# ltk-hall_main_igen.net
KiCad netlist of a schematic drawn in Altium Designer
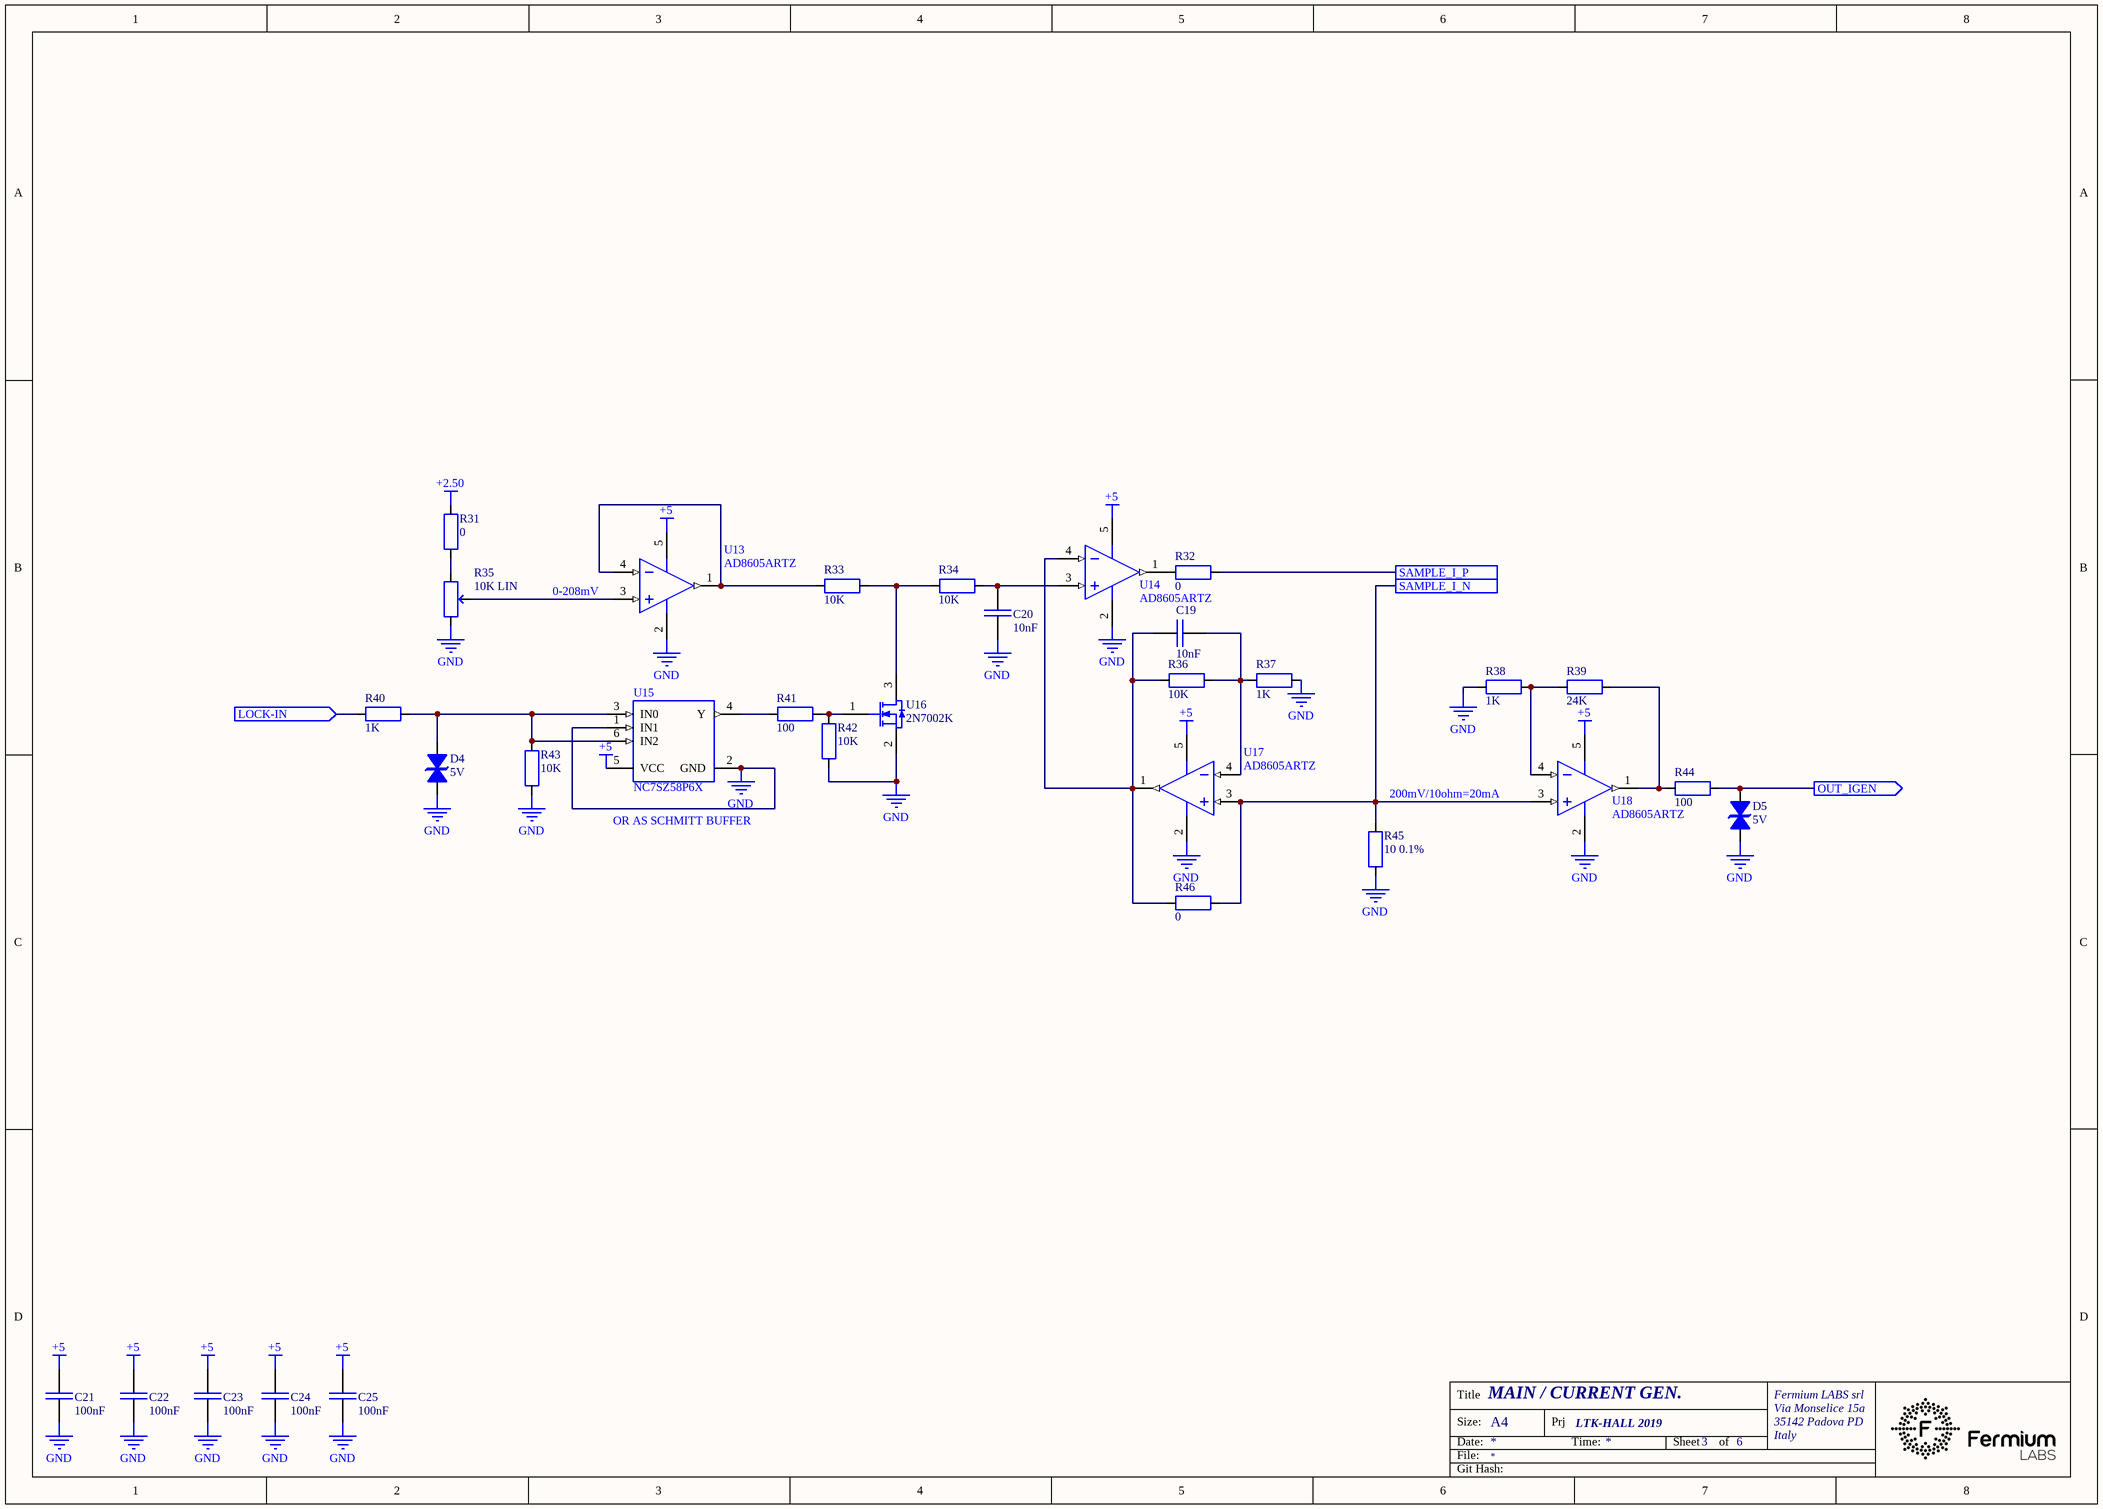
[diagram p0: ltk-hall_main_igen.SchDoc]

(export (version "E")
  (design (tool "Eeschema 10.0.6"))
  (components
    (comp (ref "C19")
      (value "10nF")
      (footprint "CAP 0603_1608")
      (description "CAP SMD MLCC 10nF 50V 0603 X7R")
      (fields (field (name "PART NUMBER") "84e1ebe1-2230-4987-8231-c47d83fa5f7f"))
      (libsource (lib "frmdblib") (part "GENERIC_C"))
    )
    (comp (ref "C20")
      (value "10nF")
      (footprint "CAP 0603_1608")
      (description "CAP SMD MLCC 10nF 50V 0603 X7R")
      (fields (field (name "PART NUMBER") "84e1ebe1-2230-4987-8231-c47d83fa5f7f"))
      (libsource (lib "frmdblib") (part "GENERIC_C"))
    )
    (comp (ref "C21")
      (value "100nF")
      (footprint "CAP 0603_1608")
      (description "CAP SMD MLCC 100nF 25V 0603 X7R")
      (fields (field (name "PART NUMBER") "02841f84-ac15-41b5-9e17-915f8f067828"))
      (libsource (lib "frmdblib") (part "GENERIC_C"))
    )
    (comp (ref "C22")
      (value "100nF")
      (footprint "CAP 0603_1608")
      (description "CAP SMD MLCC 100nF 25V 0603 X7R")
      (fields (field (name "PART NUMBER") "02841f84-ac15-41b5-9e17-915f8f067828"))
      (libsource (lib "frmdblib") (part "GENERIC_C"))
    )
    (comp (ref "C23")
      (value "100nF")
      (footprint "CAP 0603_1608")
      (description "CAP SMD MLCC 100nF 25V 0603 X7R")
      (fields (field (name "PART NUMBER") "02841f84-ac15-41b5-9e17-915f8f067828"))
      (libsource (lib "frmdblib") (part "GENERIC_C"))
    )
    (comp (ref "C24")
      (value "100nF")
      (footprint "CAP 0603_1608")
      (description "CAP SMD MLCC 100nF 25V 0603 X7R")
      (fields (field (name "PART NUMBER") "02841f84-ac15-41b5-9e17-915f8f067828"))
      (libsource (lib "frmdblib") (part "GENERIC_C"))
    )
    (comp (ref "C25")
      (value "100nF")
      (footprint "CAP 0603_1608")
      (description "CAP SMD MLCC 100nF 25V 0603 X7R")
      (fields (field (name "PART NUMBER") "02841f84-ac15-41b5-9e17-915f8f067828"))
      (libsource (lib "frmdblib") (part "GENERIC_C"))
    )
    (comp (ref "D4")
      (value "5V")
      (footprint "SOD523F")
      (description "DIODE SMD TVS 5V BIDIRECTIONAL SOD-523")
      (fields (field (name "PART NUMBER") "daa58212-38e2-4326-a156-8e48058c46f1"))
      (libsource (lib "frmdblib") (part "GENERIC_D_TVS_BI"))
    )
    (comp (ref "D5")
      (value "5V")
      (footprint "SOD523F")
      (description "DIODE SMD TVS 5V BIDIRECTIONAL SOD-523")
      (fields (field (name "PART NUMBER") "daa58212-38e2-4326-a156-8e48058c46f1"))
      (libsource (lib "frmdblib") (part "GENERIC_D_TVS_BI"))
    )
    (comp (ref "R31")
      (value "0")
      (footprint "RES 0603_1608")
      (description "RES SMD 0 OHM 5% 1/10W 0603")
      (fields (field (name "PART NUMBER") "6ae227f9-847f-4766-8522-e11a83531204"))
      (libsource (lib "frmdblib") (part "GENERIC_R"))
    )
    (comp (ref "R32")
      (value "0")
      (footprint "RES 0603_1608")
      (description "RES SMD 0 OHM 5% 1/10W 0603")
      (fields (field (name "PART NUMBER") "6ae227f9-847f-4766-8522-e11a83531204"))
      (libsource (lib "frmdblib") (part "GENERIC_R"))
    )
    (comp (ref "R33")
      (value "10K")
      (footprint "RES 0603_1608")
      (description "RES SMD 10K OHM 1% 1/10W 0603")
      (fields (field (name "PART NUMBER") "93242766-ba1d-462d-b58f-ce1dfc4129c8"))
      (libsource (lib "frmdblib") (part "GENERIC_R"))
    )
    (comp (ref "R34")
      (value "10K")
      (footprint "RES 0603_1608")
      (description "RES SMD 10K OHM 1% 1/10W 0603")
      (fields (field (name "PART NUMBER") "93242766-ba1d-462d-b58f-ce1dfc4129c8"))
      (libsource (lib "frmdblib") (part "GENERIC_R"))
    )
    (comp (ref "R35")
      (value "10K LIN")
      (footprint "2EF88547-EDEF-4A49-A522-C215618D4BC7")
      (description "POT 10K 20% SHAFT 6mmx7.4mm LIN")
      (fields (field (name "PART NUMBER") "3df905ea-1e80-4add-859d-a36edd7f106c"))
      (libsource (lib "frmdblib") (part "GENERIC_R_VAR"))
    )
    (comp (ref "R36")
      (value "10K")
      (footprint "RES 0603_1608")
      (description "RES SMD 10K OHM 1% 1/10W 0603")
      (fields (field (name "PART NUMBER") "93242766-ba1d-462d-b58f-ce1dfc4129c8"))
      (libsource (lib "frmdblib") (part "GENERIC_R"))
    )
    (comp (ref "R37")
      (value "1K")
      (footprint "RES 0603_1608")
      (description "RES SMD 1K OHM 1% 1/10W 0603")
      (fields (field (name "PART NUMBER") "a678220f-9e9d-4863-a833-9993504f723c"))
      (libsource (lib "frmdblib") (part "GENERIC_R"))
    )
    (comp (ref "R38")
      (value "1K")
      (footprint "RES 0603_1608")
      (description "RES SMD 1K OHM 1% 1/10W 0603")
      (fields (field (name "PART NUMBER") "a678220f-9e9d-4863-a833-9993504f723c"))
      (libsource (lib "frmdblib") (part "GENERIC_R"))
    )
    (comp (ref "R39")
      (value "24K")
      (footprint "RES 0603_1608")
      (description "RES SMD 24K OHM 1% 1/10W 0603")
      (fields (field (name "PART NUMBER") "89bb9559-07ab-4a9e-ba67-95cb66f30425"))
      (libsource (lib "frmdblib") (part "GENERIC_R"))
    )
    (comp (ref "R40")
      (value "1K")
      (footprint "RES 0603_1608")
      (description "RES SMD 1K OHM 1% 1/10W 0603")
      (fields (field (name "PART NUMBER") "a678220f-9e9d-4863-a833-9993504f723c"))
      (libsource (lib "frmdblib") (part "GENERIC_R"))
    )
    (comp (ref "R41")
      (value "100")
      (footprint "RES 0603_1608")
      (description "RES SMD 100 OHM 1% 1/10W 0603")
      (fields (field (name "PART NUMBER") "0a6c4b74-f837-4563-b154-6e196d753525"))
      (libsource (lib "frmdblib") (part "GENERIC_R"))
    )
    (comp (ref "R42")
      (value "10K")
      (footprint "RES 0603_1608")
      (description "RES SMD 10K OHM 1% 1/10W 0603")
      (fields (field (name "PART NUMBER") "93242766-ba1d-462d-b58f-ce1dfc4129c8"))
      (libsource (lib "frmdblib") (part "GENERIC_R"))
    )
    (comp (ref "R43")
      (value "10K")
      (footprint "RES 0603_1608")
      (description "RES SMD 10K OHM 1% 1/10W 0603")
      (fields (field (name "PART NUMBER") "93242766-ba1d-462d-b58f-ce1dfc4129c8"))
      (libsource (lib "frmdblib") (part "GENERIC_R"))
    )
    (comp (ref "R44")
      (value "100")
      (footprint "RES 0603_1608")
      (description "RES SMD 100 OHM 1% 1/10W 0603")
      (fields (field (name "PART NUMBER") "0a6c4b74-f837-4563-b154-6e196d753525"))
      (libsource (lib "frmdblib") (part "GENERIC_R"))
    )
    (comp (ref "R45")
      (value "10 0.1%")
      (footprint "RES 0603_1608")
      (description "RES SMD 10 OHM 0.1% 1/16W 25ppm  0603")
      (fields (field (name "PART NUMBER") "f0166db1-b7e4-4c18-9511-2907615c1c51"))
      (libsource (lib "frmdblib") (part "GENERIC_R"))
    )
    (comp (ref "R46")
      (value "0")
      (footprint "RES 0603_1608")
      (description "RES SMD 0 OHM 5% 1/10W 0603")
      (fields (field (name "PART NUMBER") "6ae227f9-847f-4766-8522-e11a83531204"))
      (libsource (lib "frmdblib") (part "GENERIC_R"))
    )
    (comp (ref "U13")
      (value "AD8605ARTZ")
      (footprint "A3DDA0BC-073E-4B18-9613-F713A7EC1E27")
      (description "IC OPAMP 65uV 1pA RRIO 5V 80mA SOT-23-5")
      (fields (field (name "PART NUMBER") "5610e9ea-bca8-49b2-8e5f-11409231f6a4"))
      (libsource (lib "frmdblib") (part "8096D751-9DCE-401B-B65E-AAEE0733EA70"))
    )
    (comp (ref "U14")
      (value "AD8605ARTZ")
      (footprint "A3DDA0BC-073E-4B18-9613-F713A7EC1E27")
      (description "IC OPAMP 65uV 1pA RRIO 5V 80mA SOT-23-5")
      (fields (field (name "PART NUMBER") "5610e9ea-bca8-49b2-8e5f-11409231f6a4"))
      (libsource (lib "frmdblib") (part "8096D751-9DCE-401B-B65E-AAEE0733EA70"))
    )
    (comp (ref "U15")
      (value "NC7SZ58P6X")
      (footprint "CF792C6F-51F3-4C59-9918-AD84EFC14FA6")
      (description "IC LOGIC PORT CONFIGURABLE AND, OR, NAND, NOR, XOR, BUFFER, NOT 8ns  74XX58 SC-70")
      (fields (field (name "PART NUMBER") "22da43c7-1950-42f4-bc93-10d9cca79b4d"))
      (libsource (lib "frmdblib") (part "77922C7C-4696-4818-A68A-CF4581C7C2E9"))
    )
    (comp (ref "U16")
      (value "2N7002K")
      (footprint "ON SEMI SOT-23-3")
      (description "MOSFET N-CHANNEL LOGIC LEVEL 300mA 3ohm 60V ESD-PROT 2N7002K SOT-23")
      (fields (field (name "PART NUMBER") "3a318f0a-3b94-47d9-91d5-8fc0a2f410e8"))
      (libsource (lib "frmdblib") (part "GENERIC_N_MOSFET_GSD"))
    )
    (comp (ref "U17")
      (value "AD8605ARTZ")
      (footprint "A3DDA0BC-073E-4B18-9613-F713A7EC1E27")
      (description "IC OPAMP 65uV 1pA RRIO 5V 80mA SOT-23-5")
      (fields (field (name "PART NUMBER") "5610e9ea-bca8-49b2-8e5f-11409231f6a4"))
      (libsource (lib "frmdblib") (part "8096D751-9DCE-401B-B65E-AAEE0733EA70"))
    )
    (comp (ref "U18")
      (value "AD8605ARTZ")
      (footprint "A3DDA0BC-073E-4B18-9613-F713A7EC1E27")
      (description "IC OPAMP 65uV 1pA RRIO 5V 80mA SOT-23-5")
      (fields (field (name "PART NUMBER") "5610e9ea-bca8-49b2-8e5f-11409231f6a4"))
      (libsource (lib "frmdblib") (part "8096D751-9DCE-401B-B65E-AAEE0733EA70"))
    )
  )
  (nets
    (net (code "1") (name "+2.50") (class "Default") (node (ref "R31") (pin "2") (pintype "passive")))
    (net (code "2") (name "+5") (class "Default")
      (node (ref "C21") (pin "1") (pintype "passive"))
      (node (ref "C22") (pin "1") (pintype "passive"))
      (node (ref "C23") (pin "1") (pintype "passive"))
      (node (ref "C24") (pin "1") (pintype "passive"))
      (node (ref "C25") (pin "1") (pintype "passive"))
      (node (ref "U13") (pin "5") (pinfunction "+V_5") (pintype "power_in"))
      (node (ref "U14") (pin "5") (pinfunction "+V_5") (pintype "power_in"))
      (node (ref "U15") (pin "5") (pinfunction "VCC_5") (pintype "power_in"))
      (node (ref "U17") (pin "5") (pinfunction "+V_5") (pintype "power_in"))
      (node (ref "U18") (pin "5") (pinfunction "+V_5") (pintype "power_in"))
    )
    (net (code "3") (name "/LOCK-IN") (class "Default") (node (ref "R40") (pin "2") (pintype "passive")))
    (net (code "4") (name "/OUT_IGEN") (class "Default")
      (node (ref "D5") (pin "1") (pintype "passive"))
      (node (ref "R44") (pin "2") (pintype "passive"))
    )
    (net (code "5") (name "/SAMPLE_I_N") (class "Default")
      (node (ref "R45") (pin "2") (pintype "passive"))
      (node (ref "R46") (pin "2") (pintype "passive"))
      (node (ref "U17") (pin "3") (pinfunction "+IN_3") (pintype "input"))
      (node (ref "U18") (pin "3") (pinfunction "+IN_3") (pintype "input"))
    )
    (net (code "6") (name "/SAMPLE_I_P") (class "Default") (node (ref "R32") (pin "2") (pintype "passive")))
    (net (code "7") (name "GND") (class "Default")
      (node (ref "C20") (pin "2") (pintype "passive"))
      (node (ref "C21") (pin "2") (pintype "passive"))
      (node (ref "C22") (pin "2") (pintype "passive"))
      (node (ref "C23") (pin "2") (pintype "passive"))
      (node (ref "C24") (pin "2") (pintype "passive"))
      (node (ref "C25") (pin "2") (pintype "passive"))
      (node (ref "D4") (pin "2") (pintype "passive"))
      (node (ref "D5") (pin "2") (pintype "passive"))
      (node (ref "R35") (pin "3") (pintype "passive"))
      (node (ref "R37") (pin "2") (pintype "passive"))
      (node (ref "R38") (pin "1") (pintype "passive"))
      (node (ref "R42") (pin "1") (pintype "passive"))
      (node (ref "R43") (pin "1") (pintype "passive"))
      (node (ref "R45") (pin "1") (pintype "passive"))
      (node (ref "U13") (pin "2") (pinfunction "-V_2") (pintype "power_in"))
      (node (ref "U14") (pin "2") (pinfunction "-V_2") (pintype "power_in"))
      (node (ref "U15") (pin "1") (pinfunction "IN1_1") (pintype "input"))
      (node (ref "U15") (pin "2") (pinfunction "GND_2") (pintype "power_in"))
      (node (ref "U16") (pin "2") (pinfunction "S_2") (pintype "passive"))
      (node (ref "U17") (pin "2") (pinfunction "-V_2") (pintype "power_in"))
      (node (ref "U18") (pin "2") (pinfunction "-V_2") (pintype "power_in"))
    )
    (net (code "8") (name "Net-(R31-Pad1)") (class "Default")
      (node (ref "R31") (pin "1") (pintype "passive"))
      (node (ref "R35") (pin "1") (pintype "passive"))
    )
    (net (code "9") (name "Net-(U13-+IN)") (class "Default")
      (node (ref "R35") (pin "2") (pintype "passive"))
      (node (ref "U13") (pin "3") (pinfunction "+IN_3") (pintype "input"))
    )
    (net (code "10") (name "Net-(U13--IN)") (class "Default")
      (node (ref "R33") (pin "2") (pintype "passive"))
      (node (ref "U13") (pin "1") (pinfunction "OUT_1") (pintype "output"))
      (node (ref "U13") (pin "4") (pinfunction "-IN_4") (pintype "input"))
    )
    (net (code "11") (name "Net-(U14-+IN)") (class "Default")
      (node (ref "C20") (pin "1") (pintype "passive"))
      (node (ref "R34") (pin "1") (pintype "passive"))
      (node (ref "U14") (pin "3") (pinfunction "+IN_3") (pintype "input"))
    )
    (net (code "12") (name "Net-(U14--IN)") (class "Default")
      (node (ref "C19") (pin "1") (pintype "passive"))
      (node (ref "R36") (pin "2") (pintype "passive"))
      (node (ref "R46") (pin "1") (pintype "passive"))
      (node (ref "U14") (pin "4") (pinfunction "-IN_4") (pintype "input"))
      (node (ref "U17") (pin "1") (pinfunction "OUT_1") (pintype "output"))
    )
    (net (code "13") (name "Net-(U14-OUT)") (class "Default")
      (node (ref "R32") (pin "1") (pintype "passive"))
      (node (ref "U14") (pin "1") (pinfunction "OUT_1") (pintype "output"))
    )
    (net (code "14") (name "Net-(U15-IN0)") (class "Default")
      (node (ref "D4") (pin "1") (pintype "passive"))
      (node (ref "R40") (pin "1") (pintype "passive"))
      (node (ref "R43") (pin "2") (pintype "passive"))
      (node (ref "U15") (pin "3") (pinfunction "IN0_3") (pintype "input"))
      (node (ref "U15") (pin "6") (pinfunction "IN2_6") (pintype "input"))
    )
    (net (code "15") (name "Net-(U15-Y)") (class "Default")
      (node (ref "R41") (pin "1") (pintype "passive"))
      (node (ref "U15") (pin "4") (pinfunction "Y_4") (pintype "output"))
    )
    (net (code "16") (name "Net-(U16-D)") (class "Default")
      (node (ref "R33") (pin "1") (pintype "passive"))
      (node (ref "R34") (pin "2") (pintype "passive"))
      (node (ref "U16") (pin "3") (pinfunction "D_3") (pintype "passive"))
    )
    (net (code "17") (name "Net-(U16-G)") (class "Default")
      (node (ref "R41") (pin "2") (pintype "passive"))
      (node (ref "R42") (pin "2") (pintype "passive"))
      (node (ref "U16") (pin "1") (pinfunction "G_1") (pintype "passive"))
    )
    (net (code "18") (name "Net-(U17--IN)") (class "Default")
      (node (ref "C19") (pin "2") (pintype "passive"))
      (node (ref "R36") (pin "1") (pintype "passive"))
      (node (ref "R37") (pin "1") (pintype "passive"))
      (node (ref "U17") (pin "4") (pinfunction "-IN_4") (pintype "input"))
    )
    (net (code "19") (name "Net-(U18--IN)") (class "Default")
      (node (ref "R38") (pin "2") (pintype "passive"))
      (node (ref "R39") (pin "1") (pintype "passive"))
      (node (ref "U18") (pin "4") (pinfunction "-IN_4") (pintype "input"))
    )
    (net (code "20") (name "Net-(U18-OUT)") (class "Default")
      (node (ref "R39") (pin "2") (pintype "passive"))
      (node (ref "R44") (pin "1") (pintype "passive"))
      (node (ref "U18") (pin "1") (pinfunction "OUT_1") (pintype "output"))
    )
  )
)
